# Light_Shield.net
KiCad netlist of a schematic drawn in EAGLE
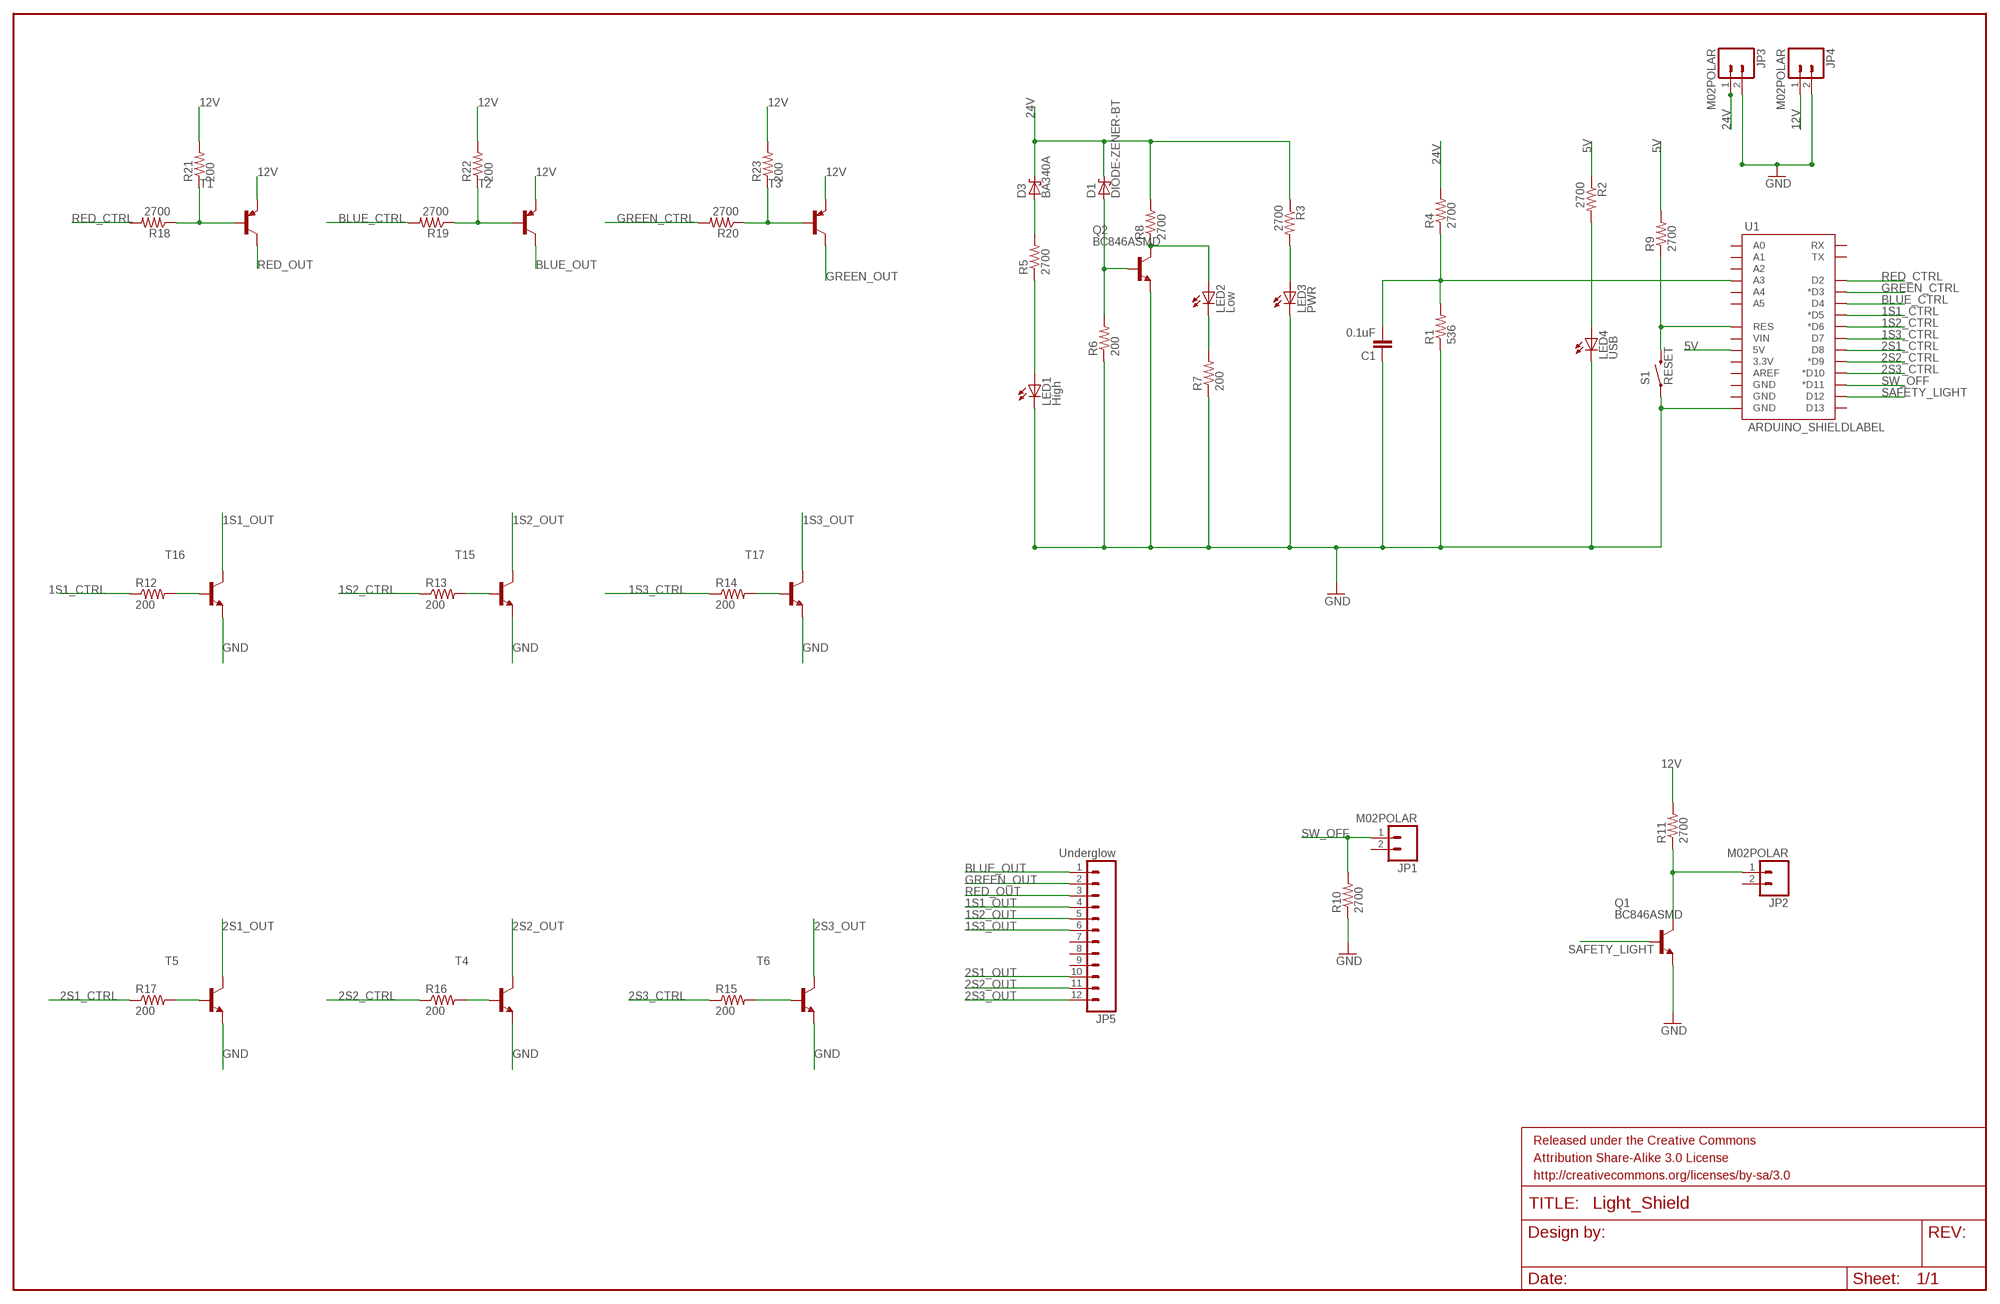
[diagram p0: schematic, sheet 1]

(export (version "E")
  (design (tool "Eeschema 10.0.6"))
  (components
    (comp (ref "C1")
      (value "0.1uF")
      (footprint "eagle-import:0402-CAP")
      (libsource (lib "eagle-import") (part "CAP0402-CAP"))
    )
    (comp (ref "D1")
      (value "DIODE-ZENER-BT")
      (footprint "eagle-import:SOD123FL")
      (libsource (lib "eagle-import") (part "SMF5.0AT1"))
    )
    (comp (ref "D3")
      (value "BA340A")
      (footprint "eagle-import:SOD123FL")
      (libsource (lib "eagle-import") (part "SMF5.0AT1"))
    )
    (comp (ref "FRAME1")
      (value "FRAME-LEDGER")
      (footprint "eagle-import:CREATIVE_COMMONS")
      (libsource (lib "eagle-import") (part "FRAME-LEDGER"))
    )
    (comp (ref "JP1")
      (value "M02POLAR")
      (footprint "eagle-import:MOLEX-1X2")
      (libsource (lib "eagle-import") (part "M02POLAR"))
    )
    (comp (ref "JP2")
      (value "M02POLAR")
      (footprint "eagle-import:MOLEX-1X2")
      (libsource (lib "eagle-import") (part "M02POLAR"))
    )
    (comp (ref "JP3")
      (value "M02POLAR")
      (footprint "eagle-import:MOLEX-1X2")
      (libsource (lib "eagle-import") (part "M02POLAR"))
    )
    (comp (ref "JP4")
      (value "M02POLAR")
      (footprint "eagle-import:MOLEX-1X2")
      (libsource (lib "eagle-import") (part "M02POLAR"))
    )
    (comp (ref "JP5")
      (value "Underglow")
      (footprint "eagle-import:1X12_LOCK_LONGPADS")
      (libsource (lib "eagle-import") (part "M12LOCK_LONGPADS"))
    )
    (comp (ref "LED1")
      (value "High")
      (footprint "eagle-import:SML0603")
      (libsource (lib "eagle-import") (part "LEDSML0603"))
    )
    (comp (ref "LED2")
      (value "Low")
      (footprint "eagle-import:SML0603")
      (libsource (lib "eagle-import") (part "LEDSML0603"))
    )
    (comp (ref "LED3")
      (value "PWR")
      (footprint "eagle-import:SML0603")
      (libsource (lib "eagle-import") (part "LEDSML0603"))
    )
    (comp (ref "LED4")
      (value "USB")
      (footprint "eagle-import:SML0603")
      (libsource (lib "eagle-import") (part "LEDSML0603"))
    )
    (comp (ref "Q1")
      (value "BC846ASMD")
      (footprint "eagle-import:SOT23")
      (libsource (lib "eagle-import") (part "BC846SMDA"))
    )
    (comp (ref "Q2")
      (value "BC846ASMD")
      (footprint "eagle-import:SOT23")
      (libsource (lib "eagle-import") (part "BC846SMDA"))
    )
    (comp (ref "R1")
      (value "536")
      (footprint "eagle-import:0402-RES")
      (libsource (lib "eagle-import") (part "RESISTOR0402-RES"))
    )
    (comp (ref "R2")
      (value "2700")
      (footprint "eagle-import:0603-RES")
      (libsource (lib "eagle-import") (part "RESISTOR0603"))
    )
    (comp (ref "R3")
      (value "2700")
      (footprint "eagle-import:0603-RES")
      (libsource (lib "eagle-import") (part "RESISTOR0603"))
    )
    (comp (ref "R4")
      (value "2700")
      (footprint "eagle-import:0603-RES")
      (libsource (lib "eagle-import") (part "RESISTOR0603"))
    )
    (comp (ref "R5")
      (value "2700")
      (footprint "eagle-import:0603-RES")
      (libsource (lib "eagle-import") (part "RESISTOR0603"))
    )
    (comp (ref "R6")
      (value "200")
      (footprint "eagle-import:0603-RES")
      (libsource (lib "eagle-import") (part "RESISTOR0603"))
    )
    (comp (ref "R7")
      (value "200")
      (footprint "eagle-import:0603-RES")
      (libsource (lib "eagle-import") (part "SparkFun-Resistors_RESISTOR0603-RES"))
    )
    (comp (ref "R8")
      (value "2700")
      (footprint "eagle-import:0603-RES")
      (libsource (lib "eagle-import") (part "SparkFun-Resistors_RESISTOR0603-RES"))
    )
    (comp (ref "R9")
      (value "2700")
      (footprint "eagle-import:0603-RES")
      (libsource (lib "eagle-import") (part "RESISTOR0603"))
    )
    (comp (ref "R10")
      (value "2700")
      (footprint "eagle-import:0603-RES")
      (libsource (lib "eagle-import") (part "RESISTOR0603"))
    )
    (comp (ref "R11")
      (value "2700")
      (footprint "eagle-import:0603-RES")
      (libsource (lib "eagle-import") (part "RESISTOR0603"))
    )
    (comp (ref "R12")
      (value "200")
      (footprint "eagle-import:0603-RES")
      (libsource (lib "eagle-import") (part "RESISTOR0603"))
    )
    (comp (ref "R13")
      (value "200")
      (footprint "eagle-import:0603-RES")
      (libsource (lib "eagle-import") (part "RESISTOR0603"))
    )
    (comp (ref "R14")
      (value "200")
      (footprint "eagle-import:0603-RES")
      (libsource (lib "eagle-import") (part "RESISTOR0603"))
    )
    (comp (ref "R15")
      (value "200")
      (footprint "eagle-import:0603-RES")
      (libsource (lib "eagle-import") (part "RESISTOR0603"))
    )
    (comp (ref "R16")
      (value "200")
      (footprint "eagle-import:0603-RES")
      (libsource (lib "eagle-import") (part "RESISTOR0603"))
    )
    (comp (ref "R17")
      (value "200")
      (footprint "eagle-import:0603-RES")
      (libsource (lib "eagle-import") (part "RESISTOR0603"))
    )
    (comp (ref "R18")
      (value "2700")
      (footprint "eagle-import:0603-RES")
      (libsource (lib "eagle-import") (part "RESISTOR0603"))
    )
    (comp (ref "R19")
      (value "2700")
      (footprint "eagle-import:0603-RES")
      (libsource (lib "eagle-import") (part "RESISTOR0603"))
    )
    (comp (ref "R20")
      (value "2700")
      (footprint "eagle-import:0603-RES")
      (libsource (lib "eagle-import") (part "RESISTOR0603"))
    )
    (comp (ref "R21")
      (value "200")
      (footprint "eagle-import:0603-RES")
      (libsource (lib "eagle-import") (part "RESISTOR0603"))
    )
    (comp (ref "R22")
      (value "200")
      (footprint "eagle-import:0603-RES")
      (libsource (lib "eagle-import") (part "RESISTOR0603"))
    )
    (comp (ref "R23")
      (value "200")
      (footprint "eagle-import:0603-RES")
      (libsource (lib "eagle-import") (part "RESISTOR0603"))
    )
    (comp (ref "S1")
      (value "RESET")
      (footprint "eagle-import:TACTILE-PTH")
      (libsource (lib "eagle-import") (part "SWITCH-MOMENTARY-2PTH"))
    )
    (comp (ref "T1")
      (value "-PNP-TO220V")
      (footprint "eagle-import:TO220V")
      (libsource (lib "eagle-import") (part "-PNP-TO220V"))
    )
    (comp (ref "T2")
      (value "-PNP-TO220V")
      (footprint "eagle-import:TO220V")
      (libsource (lib "eagle-import") (part "-PNP-TO220V"))
    )
    (comp (ref "T3")
      (value "-PNP-TO220V")
      (footprint "eagle-import:TO220V")
      (libsource (lib "eagle-import") (part "-PNP-TO220V"))
    )
    (comp (ref "T4")
      (value "-NPN-TO220V")
      (footprint "eagle-import:TO220V")
      (libsource (lib "eagle-import") (part "-NPN-TO220V"))
    )
    (comp (ref "T5")
      (value "-NPN-TO220V")
      (footprint "eagle-import:TO220V")
      (libsource (lib "eagle-import") (part "-NPN-TO220V"))
    )
    (comp (ref "T6")
      (value "-NPN-TO220V")
      (footprint "eagle-import:TO220V")
      (libsource (lib "eagle-import") (part "-NPN-TO220V"))
    )
    (comp (ref "T15")
      (value "-NPN-TO220V")
      (footprint "eagle-import:TO220V")
      (libsource (lib "eagle-import") (part "-NPN-TO220V"))
    )
    (comp (ref "T16")
      (value "-NPN-TO220V")
      (footprint "eagle-import:TO220V")
      (libsource (lib "eagle-import") (part "-NPN-TO220V"))
    )
    (comp (ref "T17")
      (value "-NPN-TO220V")
      (footprint "eagle-import:TO220V")
      (libsource (lib "eagle-import") (part "-NPN-TO220V"))
    )
    (comp (ref "U1")
      (value "ARDUINO_SHIELDLABEL")
      (footprint "eagle-import:DUEMILANOVE_SHIELD")
      (libsource (lib "eagle-import") (part "ARDUINO_SHIELDLABEL"))
    )
  )
  (nets
    (net (code "1") (name "/1S1_CTRL") (class "Default")
      (node (ref "R12") (pin "1") (pinfunction "1_1") (pintype "passive"))
      (node (ref "U1") (pin "D5") (pinfunction "*D5_D5") (pintype "bidirectional"))
    )
    (net (code "2") (name "/1S1_OUT") (class "Default")
      (node (ref "JP5") (pin "4") (pinfunction "4_4") (pintype "passive"))
      (node (ref "T16") (pin "2") (pinfunction "C_2") (pintype "passive"))
    )
    (net (code "3") (name "/1S2_CTRL") (class "Default")
      (node (ref "R13") (pin "1") (pinfunction "1_1") (pintype "passive"))
      (node (ref "U1") (pin "D6") (pinfunction "*D6_D6") (pintype "bidirectional"))
    )
    (net (code "4") (name "/1S2_OUT") (class "Default")
      (node (ref "JP5") (pin "5") (pinfunction "5_5") (pintype "passive"))
      (node (ref "T15") (pin "2") (pinfunction "C_2") (pintype "passive"))
    )
    (net (code "5") (name "/1S3_CTRL") (class "Default")
      (node (ref "R14") (pin "1") (pinfunction "1_1") (pintype "passive"))
      (node (ref "U1") (pin "D7") (pinfunction "D7_D7") (pintype "bidirectional"))
    )
    (net (code "6") (name "/1S3_OUT") (class "Default")
      (node (ref "JP5") (pin "6") (pinfunction "6_6") (pintype "passive"))
      (node (ref "T17") (pin "2") (pinfunction "C_2") (pintype "passive"))
    )
    (net (code "7") (name "/2S1_CTRL") (class "Default")
      (node (ref "R17") (pin "1") (pinfunction "1_1") (pintype "passive"))
      (node (ref "U1") (pin "D8") (pinfunction "D8_D8") (pintype "bidirectional"))
    )
    (net (code "8") (name "/2S1_OUT") (class "Default")
      (node (ref "JP5") (pin "10") (pinfunction "10_10") (pintype "passive"))
      (node (ref "T5") (pin "2") (pinfunction "C_2") (pintype "passive"))
    )
    (net (code "9") (name "/2S2_CTRL") (class "Default")
      (node (ref "R16") (pin "1") (pinfunction "1_1") (pintype "passive"))
      (node (ref "U1") (pin "D9") (pinfunction "*D9_D9") (pintype "bidirectional"))
    )
    (net (code "10") (name "/2S2_OUT") (class "Default")
      (node (ref "JP5") (pin "11") (pinfunction "11_11") (pintype "passive"))
      (node (ref "T4") (pin "2") (pinfunction "C_2") (pintype "passive"))
    )
    (net (code "11") (name "/2S3_CTRL") (class "Default")
      (node (ref "R15") (pin "1") (pinfunction "1_1") (pintype "passive"))
      (node (ref "U1") (pin "D10") (pinfunction "*D10_D10") (pintype "bidirectional"))
    )
    (net (code "12") (name "/2S3_OUT") (class "Default")
      (node (ref "JP5") (pin "12") (pinfunction "12_12") (pintype "passive"))
      (node (ref "T6") (pin "2") (pinfunction "C_2") (pintype "passive"))
    )
    (net (code "13") (name "/5V") (class "Default")
      (node (ref "R2") (pin "1") (pinfunction "1_1") (pintype "passive"))
      (node (ref "R9") (pin "2") (pinfunction "2_2") (pintype "passive"))
      (node (ref "U1") (pin "5V") (pinfunction "5V_5V") (pintype "bidirectional"))
    )
    (net (code "14") (name "/12V") (class "Default")
      (node (ref "JP4") (pin "1") (pinfunction "1_1") (pintype "passive"))
      (node (ref "R11") (pin "2") (pinfunction "2_2") (pintype "passive"))
      (node (ref "R21") (pin "2") (pinfunction "2_2") (pintype "passive"))
      (node (ref "R22") (pin "2") (pinfunction "2_2") (pintype "passive"))
      (node (ref "R23") (pin "2") (pinfunction "2_2") (pintype "passive"))
      (node (ref "T1") (pin "3") (pinfunction "E_3") (pintype "passive"))
      (node (ref "T2") (pin "3") (pinfunction "E_3") (pintype "passive"))
      (node (ref "T3") (pin "3") (pinfunction "E_3") (pintype "passive"))
    )
    (net (code "15") (name "/24V") (class "Default")
      (node (ref "D1") (pin "C") (pinfunction "C_C") (pintype "passive"))
      (node (ref "D3") (pin "C") (pinfunction "C_C") (pintype "passive"))
      (node (ref "JP3") (pin "1") (pinfunction "1_1") (pintype "passive"))
      (node (ref "R3") (pin "1") (pinfunction "1_1") (pintype "passive"))
      (node (ref "R4") (pin "2") (pinfunction "2_2") (pintype "passive"))
      (node (ref "R8") (pin "2") (pinfunction "2_2") (pintype "passive"))
    )
    (net (code "16") (name "/BLUE_CTRL") (class "Default")
      (node (ref "R19") (pin "2") (pinfunction "2_2") (pintype "passive"))
      (node (ref "U1") (pin "D4") (pinfunction "D4_D4") (pintype "bidirectional"))
    )
    (net (code "17") (name "/BLUE_OUT") (class "Default")
      (node (ref "JP5") (pin "1") (pinfunction "1_1") (pintype "passive"))
      (node (ref "T2") (pin "2") (pinfunction "C_2") (pintype "passive"))
    )
    (net (code "18") (name "/GREEN_CTRL") (class "Default")
      (node (ref "R20") (pin "2") (pinfunction "2_2") (pintype "passive"))
      (node (ref "U1") (pin "D3") (pinfunction "*D3_D3") (pintype "bidirectional"))
    )
    (net (code "19") (name "/GREEN_OUT") (class "Default")
      (node (ref "JP5") (pin "2") (pinfunction "2_2") (pintype "passive"))
      (node (ref "T3") (pin "2") (pinfunction "C_2") (pintype "passive"))
    )
    (net (code "20") (name "/RED_CTRL") (class "Default")
      (node (ref "R18") (pin "2") (pinfunction "2_2") (pintype "passive"))
      (node (ref "U1") (pin "D2") (pinfunction "D2_D2") (pintype "bidirectional"))
    )
    (net (code "21") (name "/RED_OUT") (class "Default")
      (node (ref "JP5") (pin "3") (pinfunction "3_3") (pintype "passive"))
      (node (ref "T1") (pin "2") (pinfunction "C_2") (pintype "passive"))
    )
    (net (code "22") (name "/SAFETY_LIGHT") (class "Default")
      (node (ref "Q1") (pin "1") (pinfunction "B_1") (pintype "passive"))
      (node (ref "U1") (pin "D12") (pinfunction "D12_D12") (pintype "bidirectional"))
    )
    (net (code "23") (name "/SW_OFF") (class "Default")
      (node (ref "JP1") (pin "1") (pinfunction "1_1") (pintype "passive"))
      (node (ref "R10") (pin "2") (pinfunction "2_2") (pintype "passive"))
      (node (ref "U1") (pin "D11") (pinfunction "*D11_D11") (pintype "bidirectional"))
    )
    (net (code "24") (name "GND") (class "Default")
      (node (ref "C1") (pin "1") (pinfunction "1_1") (pintype "passive"))
      (node (ref "JP3") (pin "2") (pinfunction "2_2") (pintype "passive"))
      (node (ref "JP4") (pin "2") (pinfunction "2_2") (pintype "passive"))
      (node (ref "LED1") (pin "C") (pinfunction "C_C") (pintype "passive"))
      (node (ref "LED3") (pin "C") (pinfunction "C_C") (pintype "passive"))
      (node (ref "LED4") (pin "C") (pinfunction "C_C") (pintype "passive"))
      (node (ref "Q1") (pin "2") (pinfunction "E_2") (pintype "passive"))
      (node (ref "Q2") (pin "2") (pinfunction "E_2") (pintype "passive"))
      (node (ref "R1") (pin "1") (pinfunction "1_1") (pintype "passive"))
      (node (ref "R10") (pin "1") (pinfunction "1_1") (pintype "passive"))
      (node (ref "R6") (pin "1") (pinfunction "1_1") (pintype "passive"))
      (node (ref "R7") (pin "1") (pinfunction "1_1") (pintype "passive"))
      (node (ref "S1") (pin "1") (pinfunction "1_1") (pintype "passive"))
      (node (ref "T15") (pin "3") (pinfunction "E_3") (pintype "passive"))
      (node (ref "T16") (pin "3") (pinfunction "E_3") (pintype "passive"))
      (node (ref "T17") (pin "3") (pinfunction "E_3") (pintype "passive"))
      (node (ref "T4") (pin "3") (pinfunction "E_3") (pintype "passive"))
      (node (ref "T5") (pin "3") (pinfunction "E_3") (pintype "passive"))
      (node (ref "T6") (pin "3") (pinfunction "E_3") (pintype "passive"))
      (node (ref "U1") (pin "GND@0") (pinfunction "GND_GND@0") (pintype "bidirectional"))
    )
    (net (code "25") (name "Net-(C1-Pad2)") (class "Default")
      (node (ref "C1") (pin "2") (pinfunction "2_2") (pintype "passive"))
      (node (ref "R1") (pin "2") (pinfunction "2_2") (pintype "passive"))
      (node (ref "R4") (pin "1") (pinfunction "1_1") (pintype "passive"))
      (node (ref "U1") (pin "A3") (pinfunction "A3_A3") (pintype "bidirectional"))
    )
    (net (code "26") (name "Net-(D3-PadA)") (class "Default")
      (node (ref "D3") (pin "A") (pinfunction "A_A") (pintype "passive"))
      (node (ref "R5") (pin "2") (pinfunction "2_2") (pintype "passive"))
    )
    (net (code "27") (name "Net-(LED1-PadA)") (class "Default")
      (node (ref "LED1") (pin "A") (pinfunction "A_A") (pintype "passive"))
      (node (ref "R5") (pin "1") (pinfunction "1_1") (pintype "passive"))
    )
    (net (code "28") (name "Net-(LED2-PadC)") (class "Default")
      (node (ref "LED2") (pin "C") (pinfunction "C_C") (pintype "passive"))
      (node (ref "R7") (pin "2") (pinfunction "2_2") (pintype "passive"))
    )
    (net (code "29") (name "Net-(LED3-PadA)") (class "Default")
      (node (ref "LED3") (pin "A") (pinfunction "A_A") (pintype "passive"))
      (node (ref "R3") (pin "2") (pinfunction "2_2") (pintype "passive"))
    )
    (net (code "30") (name "Net-(LED4-PadA)") (class "Default")
      (node (ref "LED4") (pin "A") (pinfunction "A_A") (pintype "passive"))
      (node (ref "R2") (pin "2") (pinfunction "2_2") (pintype "passive"))
    )
    (net (code "31") (name "Net-(Q1-C)") (class "Default")
      (node (ref "JP2") (pin "1") (pinfunction "1_1") (pintype "passive"))
      (node (ref "Q1") (pin "3") (pinfunction "C_3") (pintype "passive"))
      (node (ref "R11") (pin "1") (pinfunction "1_1") (pintype "passive"))
    )
    (net (code "32") (name "Net-(Q2-B)") (class "Default")
      (node (ref "D1") (pin "A") (pinfunction "A_A") (pintype "passive"))
      (node (ref "Q2") (pin "1") (pinfunction "B_1") (pintype "passive"))
      (node (ref "R6") (pin "2") (pinfunction "2_2") (pintype "passive"))
    )
    (net (code "33") (name "Net-(Q2-C)") (class "Default")
      (node (ref "LED2") (pin "A") (pinfunction "A_A") (pintype "passive"))
      (node (ref "Q2") (pin "3") (pinfunction "C_3") (pintype "passive"))
      (node (ref "R8") (pin "1") (pinfunction "1_1") (pintype "passive"))
    )
    (net (code "34") (name "Net-(S1-2)") (class "Default")
      (node (ref "R9") (pin "1") (pinfunction "1_1") (pintype "passive"))
      (node (ref "S1") (pin "3") (pinfunction "2_3") (pintype "passive"))
      (node (ref "U1") (pin "RES") (pinfunction "RES_RES") (pintype "bidirectional"))
    )
    (net (code "35") (name "Net-(T1-B)") (class "Default")
      (node (ref "R18") (pin "1") (pinfunction "1_1") (pintype "passive"))
      (node (ref "R21") (pin "1") (pinfunction "1_1") (pintype "passive"))
      (node (ref "T1") (pin "1") (pinfunction "B_1") (pintype "passive"))
    )
    (net (code "36") (name "Net-(T2-B)") (class "Default")
      (node (ref "R19") (pin "1") (pinfunction "1_1") (pintype "passive"))
      (node (ref "R22") (pin "1") (pinfunction "1_1") (pintype "passive"))
      (node (ref "T2") (pin "1") (pinfunction "B_1") (pintype "passive"))
    )
    (net (code "37") (name "Net-(T3-B)") (class "Default")
      (node (ref "R20") (pin "1") (pinfunction "1_1") (pintype "passive"))
      (node (ref "R23") (pin "1") (pinfunction "1_1") (pintype "passive"))
      (node (ref "T3") (pin "1") (pinfunction "B_1") (pintype "passive"))
    )
    (net (code "38") (name "Net-(T4-B)") (class "Default")
      (node (ref "R16") (pin "2") (pinfunction "2_2") (pintype "passive"))
      (node (ref "T4") (pin "1") (pinfunction "B_1") (pintype "passive"))
    )
    (net (code "39") (name "Net-(T5-B)") (class "Default")
      (node (ref "R17") (pin "2") (pinfunction "2_2") (pintype "passive"))
      (node (ref "T5") (pin "1") (pinfunction "B_1") (pintype "passive"))
    )
    (net (code "40") (name "Net-(T6-B)") (class "Default")
      (node (ref "R15") (pin "2") (pinfunction "2_2") (pintype "passive"))
      (node (ref "T6") (pin "1") (pinfunction "B_1") (pintype "passive"))
    )
    (net (code "41") (name "Net-(T15-B)") (class "Default")
      (node (ref "R13") (pin "2") (pinfunction "2_2") (pintype "passive"))
      (node (ref "T15") (pin "1") (pinfunction "B_1") (pintype "passive"))
    )
    (net (code "42") (name "Net-(T16-B)") (class "Default")
      (node (ref "R12") (pin "2") (pinfunction "2_2") (pintype "passive"))
      (node (ref "T16") (pin "1") (pinfunction "B_1") (pintype "passive"))
    )
    (net (code "43") (name "Net-(T17-B)") (class "Default")
      (node (ref "R14") (pin "2") (pinfunction "2_2") (pintype "passive"))
      (node (ref "T17") (pin "1") (pinfunction "B_1") (pintype "passive"))
    )
    (net (code "44") (name "unconnected-(JP1-Pad2)") (class "Default")
      (node (ref "JP1") (pin "2") (pinfunction "2_2") (pintype "passive"))
    )
    (net (code "45") (name "unconnected-(JP2-Pad2)") (class "Default")
      (node (ref "JP2") (pin "2") (pinfunction "2_2") (pintype "passive"))
    )
    (net (code "46") (name "unconnected-(JP5-Pad7)") (class "Default")
      (node (ref "JP5") (pin "7") (pinfunction "7_7") (pintype "passive"))
    )
    (net (code "47") (name "unconnected-(JP5-Pad8)") (class "Default")
      (node (ref "JP5") (pin "8") (pinfunction "8_8") (pintype "passive"))
    )
    (net (code "48") (name "unconnected-(JP5-Pad9)") (class "Default")
      (node (ref "JP5") (pin "9") (pinfunction "9_9") (pintype "passive"))
    )
    (net (code "49") (name "unconnected-(U1-GND-PadGND@1)") (class "Default")
      (node (ref "U1") (pin "GND@1") (pinfunction "GND_GND@1") (pintype "bidirectional"))
    )
    (net (code "50") (name "unconnected-(U1-GND-PadGND@2)") (class "Default")
      (node (ref "U1") (pin "GND@2") (pinfunction "GND_GND@2") (pintype "bidirectional"))
    )
    (net (code "51") (name "unconnected-(U1-Pad3.3V)") (class "Default")
      (node (ref "U1") (pin "3.3V") (pinfunction "3.3V_3.3V") (pintype "bidirectional"))
    )
    (net (code "52") (name "unconnected-(U1-PadA0)") (class "Default")
      (node (ref "U1") (pin "A0") (pinfunction "A0_A0") (pintype "bidirectional"))
    )
    (net (code "53") (name "unconnected-(U1-PadA1)") (class "Default")
      (node (ref "U1") (pin "A1") (pinfunction "A1_A1") (pintype "bidirectional"))
    )
    (net (code "54") (name "unconnected-(U1-PadA2)") (class "Default")
      (node (ref "U1") (pin "A2") (pinfunction "A2_A2") (pintype "bidirectional"))
    )
    (net (code "55") (name "unconnected-(U1-PadA4)") (class "Default")
      (node (ref "U1") (pin "A4") (pinfunction "A4_A4") (pintype "bidirectional"))
    )
    (net (code "56") (name "unconnected-(U1-PadA5)") (class "Default")
      (node (ref "U1") (pin "A5") (pinfunction "A5_A5") (pintype "bidirectional"))
    )
    (net (code "57") (name "unconnected-(U1-PadAREF)") (class "Default")
      (node (ref "U1") (pin "AREF") (pinfunction "AREF_AREF") (pintype "bidirectional"))
    )
    (net (code "58") (name "unconnected-(U1-PadD13)") (class "Default")
      (node (ref "U1") (pin "D13") (pinfunction "D13_D13") (pintype "bidirectional"))
    )
    (net (code "59") (name "unconnected-(U1-PadRX)") (class "Default")
      (node (ref "U1") (pin "RX") (pinfunction "RX_RX") (pintype "bidirectional"))
    )
    (net (code "60") (name "unconnected-(U1-PadTX)") (class "Default")
      (node (ref "U1") (pin "TX") (pinfunction "TX_TX") (pintype "bidirectional"))
    )
    (net (code "61") (name "unconnected-(U1-PadVIN)") (class "Default")
      (node (ref "U1") (pin "VIN") (pinfunction "VIN_VIN") (pintype "bidirectional"))
    )
  )
)
